# SBUS_JTAG.net
KiCad netlist of a schematic drawn in Altium Designer
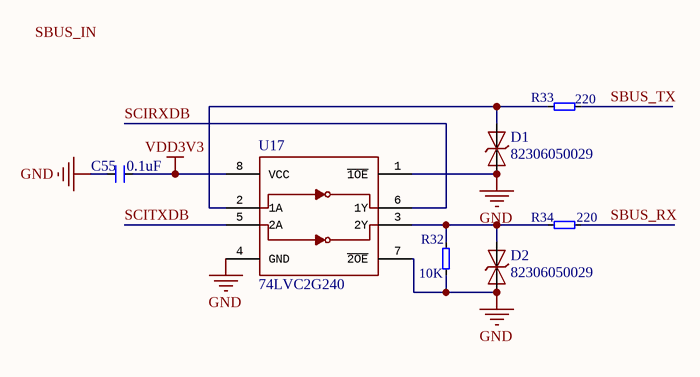
[diagram p0: SBUS&JTAG.SchDoc]

(export (version "E")
  (design (tool "Eeschema 10.0.6"))
  (components
    (comp (ref "C55") (value "0.1uF") (footprint "0603C") (libsource (lib "研发中心原理图库文件") (part "C")))
    (comp (ref "D1")
      (value "82306050029")
      (footprint "0603R")
      (libsource (lib "研发中心原理图库文件") (part "DIODE-TVS/Bidirectional"))
    )
    (comp (ref "D2")
      (value "82306050029")
      (footprint "0603R")
      (libsource (lib "研发中心原理图库文件") (part "DIODE-TVS/Bidirectional"))
    )
    (comp (ref "R32") (value "10K") (footprint "0603R") (libsource (lib "研发中心原理图库文件") (part "R")))
    (comp (ref "R33") (value "220") (footprint "0603R") (libsource (lib "研发中心原理图库文件") (part "R")))
    (comp (ref "R34") (value "220") (footprint "0603R") (libsource (lib "研发中心原理图库文件") (part "R")))
    (comp (ref "U17")
      (value "74LVC2G240")
      (footprint "VSSOP8-0.5")
      (libsource (lib "研发中心原理图库文件") (part "74LVC2G240"))
    )
  )
  (nets
    (net (code "2") (name "/SBUS_RX") (class "Default") (node (ref "R34") (pin "1") (pintype "passive")))
    (net (code "3") (name "/SBUS_TX") (class "Default") (node (ref "R33") (pin "1") (pintype "passive")))
    (net (code "4") (name "/SCIRXDB") (class "Default")
      (node (ref "U17") (pin "6") (pinfunction "1Y_6") (pintype "passive"))
    )
    (net (code "5") (name "/SCITXDB") (class "Default")
      (node (ref "U17") (pin "5") (pinfunction "2A_5") (pintype "passive"))
    )
    (net (code "6") (name "GND") (class "Default")
      (node (ref "C55") (pin "2") (pintype "passive"))
      (node (ref "D1") (pin "2") (pinfunction "2_2") (pintype "passive"))
      (node (ref "D2") (pin "2") (pinfunction "2_2") (pintype "passive"))
      (node (ref "R32") (pin "2") (pintype "passive"))
      (node (ref "U17") (pin "1") (pinfunction "~{1OE}_1") (pintype "passive"))
      (node (ref "U17") (pin "4") (pinfunction "GND_4") (pintype "open_emitter"))
      (node (ref "U17") (pin "7") (pinfunction "~{2OE}_7") (pintype "passive"))
    )
    (net (code "7") (name "Net-(U17-1A)") (class "Default")
      (node (ref "D1") (pin "1") (pinfunction "1_1") (pintype "passive"))
      (node (ref "R33") (pin "2") (pintype "passive"))
      (node (ref "U17") (pin "2") (pinfunction "1A_2") (pintype "passive"))
    )
    (net (code "8") (name "Net-(U17-2Y)") (class "Default")
      (node (ref "D2") (pin "1") (pinfunction "1_1") (pintype "passive"))
      (node (ref "R32") (pin "1") (pintype "passive"))
      (node (ref "R34") (pin "2") (pintype "passive"))
      (node (ref "U17") (pin "3") (pinfunction "2Y_3") (pintype "passive"))
    )
    (net (code "9") (name "VDD3V3") (class "Default")
      (node (ref "C55") (pin "1") (pintype "passive"))
      (node (ref "U17") (pin "8") (pinfunction "VCC_8") (pintype "open_emitter"))
    )
  )
)
